# CopterControl_3D.net
KiCad netlist of a schematic drawn in Altium Designer
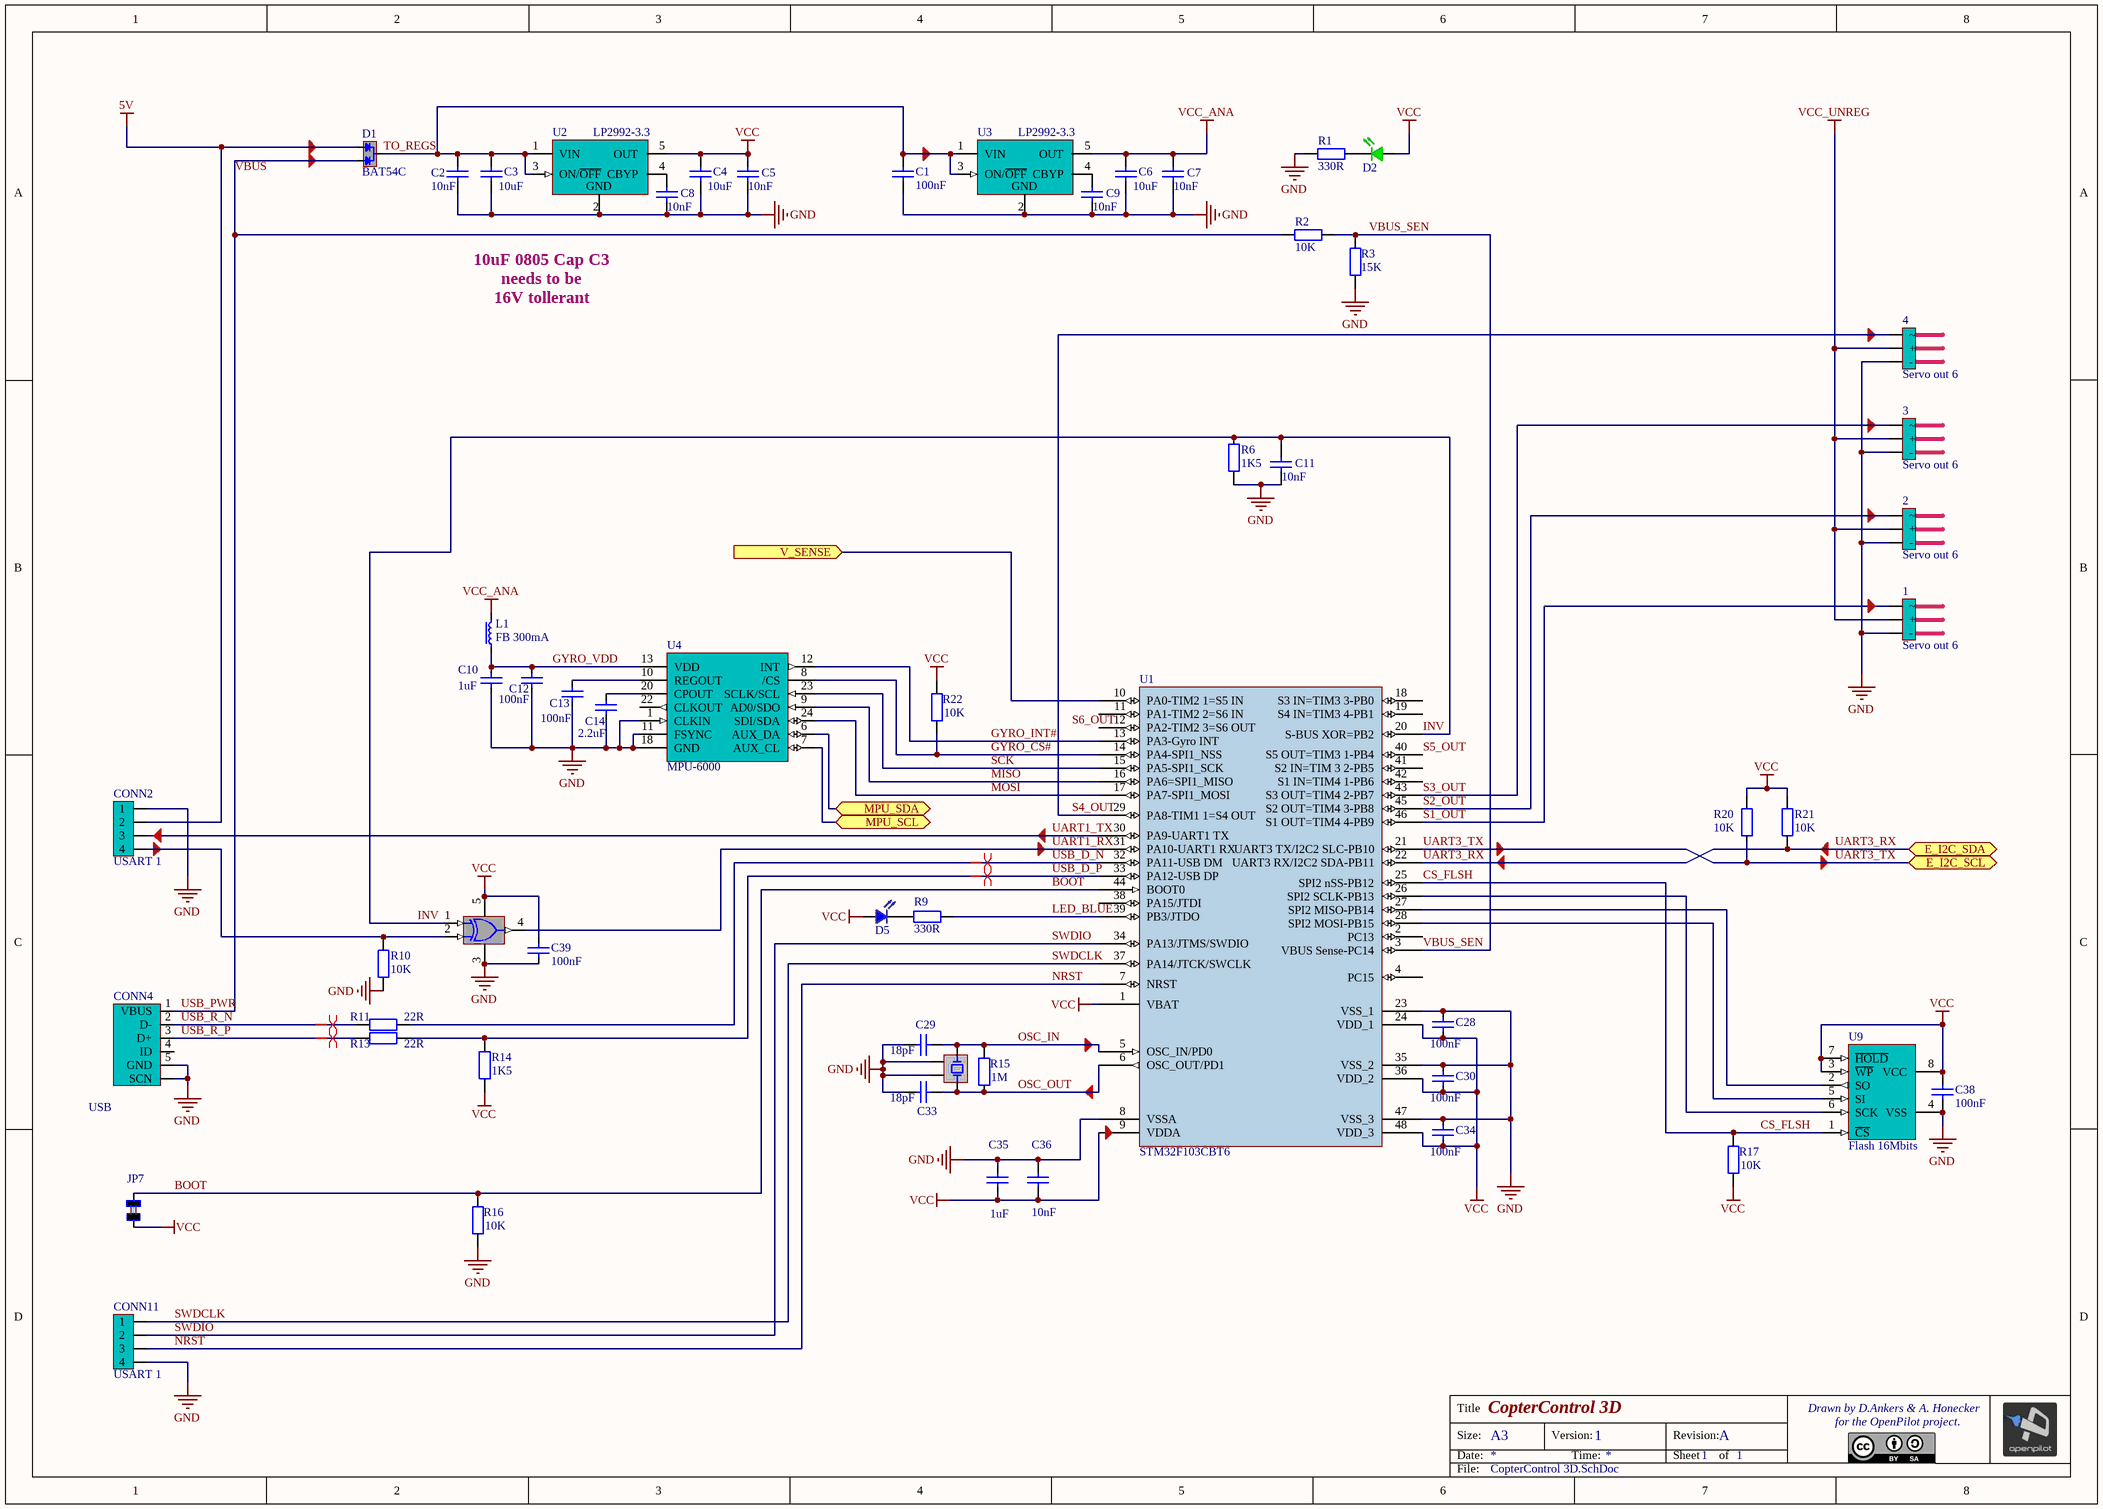
[diagram p0: CopterControl 3D.SchDoc]

(export (version "E")
  (design (tool "Eeschema 10.0.6"))
  (components
    (comp (ref "1")
      (value "Servo out 6")
      (footprint "SIP3 - 0.1")
      (description "Header, 3-Pin, 0.1\"")
      (fields (field (name "MANUFACTURER") "Generic Components"))
      (libsource (lib "CopterControl 3D") (part "Hdr 3 Pin 0.1"))
    )
    (comp (ref "2")
      (value "Servo out 6")
      (footprint "SIP3 - 0.1")
      (description "Header, 3-Pin, 0.1\"")
      (fields (field (name "MANUFACTURER") "Generic Components"))
      (libsource (lib "CopterControl 3D") (part "Hdr 3 Pin 0.1"))
    )
    (comp (ref "3")
      (value "Servo out 6")
      (footprint "SIP3 - 0.1")
      (description "Header, 3-Pin, 0.1\"")
      (fields (field (name "MANUFACTURER") "Generic Components"))
      (libsource (lib "CopterControl 3D") (part "Hdr 3 Pin 0.1"))
    )
    (comp (ref "4")
      (value "Servo out 6")
      (footprint "SIP3 - 0.1")
      (description "Header, 3-Pin, 0.1\"")
      (fields (field (name "MANUFACTURER") "Generic Components"))
      (libsource (lib "CopterControl 3D") (part "Hdr 3 Pin 0.1"))
    )
    (comp (ref "C1")
      (value "100nF")
      (footprint "CAP603N")
      (description "Capacitor SMD")
      (fields (field (name "Comment") "Cap603") (field (name "PUBLISHER") "The OpenPilot Project"))
      (libsource (lib "") (part "Cap603_1"))
    )
    (comp (ref "C2")
      (value "10nF")
      (footprint "CAP603L")
      (description "Capacitor SMD")
      (fields (field (name "Comment") "Cap603") (field (name "PUBLISHER") "The OpenPilot Project"))
      (libsource (lib "") (part "Cap603_1"))
    )
    (comp (ref "C3")
      (value "10uF")
      (footprint "CAP805L")
      (description "Capacitor SMD")
      (fields (field (name "Comment") "Cap805") (field (name "PUBLISHER") "The OpenPilot Project"))
      (libsource (lib "OpenPilot") (part "Cap805"))
    )
    (comp (ref "C4")
      (value "10uF")
      (footprint "CAP805L")
      (description "Capacitor SMD")
      (fields (field (name "Comment") "Cap805") (field (name "PUBLISHER") "The OpenPilot Project"))
      (libsource (lib "OpenPilot") (part "Cap805"))
    )
    (comp (ref "C5")
      (value "10nF")
      (footprint "CAP603N")
      (description "Capacitor SMD")
      (fields (field (name "Comment") "Cap603") (field (name "PUBLISHER") "The OpenPilot Project"))
      (libsource (lib "") (part "Cap603_1"))
    )
    (comp (ref "C6")
      (value "10uF")
      (footprint "CAP805L")
      (description "Capacitor SMD")
      (fields (field (name "Comment") "Cap805") (field (name "PUBLISHER") "The OpenPilot Project"))
      (libsource (lib "OpenPilot") (part "Cap805"))
    )
    (comp (ref "C7")
      (value "10nF")
      (footprint "CAP603N")
      (description "Capacitor SMD")
      (fields (field (name "Comment") "Cap603") (field (name "PUBLISHER") "The OpenPilot Project"))
      (libsource (lib "") (part "Cap603_1"))
    )
    (comp (ref "C8")
      (value "10nF")
      (footprint "CAP603N")
      (description "Capacitor SMD")
      (fields (field (name "Comment") "Cap603") (field (name "PUBLISHER") "The OpenPilot Project"))
      (libsource (lib "") (part "Cap603_1"))
    )
    (comp (ref "C9")
      (value "10nF")
      (footprint "CAP603N")
      (description "Capacitor SMD")
      (fields (field (name "Comment") "Cap603") (field (name "PUBLISHER") "The OpenPilot Project"))
      (libsource (lib "") (part "Cap603_1"))
    )
    (comp (ref "C10")
      (value "1uF")
      (footprint "CAP603L")
      (description "Capacitor SMD")
      (fields (field (name "Comment") "Cap603") (field (name "PUBLISHER") "The OpenPilot Project"))
      (libsource (lib "OpenPilot") (part "Cap603"))
    )
    (comp (ref "C11")
      (value "10nF")
      (footprint "CAP603N")
      (description "Capacitor SMD")
      (fields (field (name "Comment") "Cap603") (field (name "PUBLISHER") "The OpenPilot Project"))
      (libsource (lib "") (part "Cap603_1"))
    )
    (comp (ref "C12")
      (value "100nF")
      (footprint "CAP603L")
      (description "Capacitor SMD")
      (fields (field (name "Comment") "Cap603") (field (name "PUBLISHER") "The OpenPilot Project"))
      (libsource (lib "OpenPilot") (part "Cap603"))
    )
    (comp (ref "C13")
      (value "100nF")
      (footprint "CAP603L")
      (description "Capacitor SMD")
      (fields (field (name "Comment") "Cap603") (field (name "PUBLISHER") "The OpenPilot Project"))
      (libsource (lib "OpenPilot") (part "Cap603"))
    )
    (comp (ref "C14")
      (value "2.2uF")
      (footprint "CAP603L")
      (description "Capacitor SMD")
      (fields (field (name "Comment") "Cap603") (field (name "PUBLISHER") "The OpenPilot Project"))
      (libsource (lib "OpenPilot") (part "Cap603"))
    )
    (comp (ref "C28")
      (value "100nF")
      (footprint "CAP603N")
      (description "Capacitor SMD")
      (fields (field (name "Comment") "Cap603") (field (name "PUBLISHER") "The OpenPilot Project"))
      (libsource (lib "OpenPilot") (part "Cap603"))
    )
    (comp (ref "C29")
      (value "18pF")
      (footprint "CAP603N")
      (description "Capacitor SMD")
      (fields (field (name "Comment") "Cap603") (field (name "PUBLISHER") "The OpenPilot Project"))
      (libsource (lib "") (part "Cap603_1"))
    )
    (comp (ref "C30")
      (value "100nF")
      (footprint "CAP603N")
      (description "Capacitor SMD")
      (fields (field (name "Comment") "Cap603") (field (name "PUBLISHER") "The OpenPilot Project"))
      (libsource (lib "OpenPilot") (part "Cap603"))
    )
    (comp (ref "C33")
      (value "18pF")
      (footprint "CAP603N")
      (description "Capacitor SMD")
      (fields (field (name "Comment") "Cap603") (field (name "PUBLISHER") "The OpenPilot Project"))
      (libsource (lib "") (part "Cap603_1"))
    )
    (comp (ref "C34")
      (value "100nF")
      (footprint "CAP603N")
      (description "Capacitor SMD")
      (fields (field (name "Comment") "Cap603") (field (name "PUBLISHER") "The OpenPilot Project"))
      (libsource (lib "OpenPilot") (part "Cap603"))
    )
    (comp (ref "C35")
      (value "1uF")
      (footprint "CAP603L")
      (description "Capacitor SMD")
      (fields (field (name "Comment") "Cap603") (field (name "PUBLISHER") "The OpenPilot Project"))
      (libsource (lib "OpenPilot") (part "Cap603"))
    )
    (comp (ref "C36")
      (value "10nF")
      (footprint "CAP603N")
      (description "Capacitor SMD")
      (fields (field (name "Comment") "Cap603") (field (name "PUBLISHER") "The OpenPilot Project"))
      (libsource (lib "") (part "Cap603_1"))
    )
    (comp (ref "C38")
      (value "100nF")
      (footprint "CAP603N")
      (description "Capacitor SMD")
      (fields (field (name "Comment") "Cap603") (field (name "PUBLISHER") "The OpenPilot Project"))
      (libsource (lib "") (part "Cap603_1"))
    )
    (comp (ref "C39")
      (value "100nF")
      (footprint "CAP603N")
      (description "Capacitor SMD")
      (fields (field (name "Comment") "Cap603") (field (name "PUBLISHER") "The OpenPilot Project"))
      (libsource (lib "OpenPilot") (part "Cap603"))
    )
    (comp (ref "CONN2")
      (value "USART 1")
      (footprint "JST SH 4 Pin Side Entry")
      (description "JST-SH 4-pin Side Entry Socket")
      (fields (field (name "MANUFACTURER") "Generic Components"))
      (libsource (lib "CopterControl 3D") (part "JST-SH 4-pin Side Entry Socket"))
    )
    (comp (ref "CONN4")
      (value "USB")
      (footprint "USB SMD")
      (description "USB Type-B SMT Socket")
      (libsource (lib "CopterControl 3D") (part "USB_SMT_B"))
    )
    (comp (ref "CONN11")
      (value "USART 1")
      (footprint "JST SH 4 Pin Side Entry")
      (description "JST-SH 4-pin Side Entry Socket")
      (fields (field (name "MANUFACTURER") "Generic Components"))
      (libsource (lib "CopterControl 3D") (part "JST-SH 4-pin Side Entry Socket"))
    )
    (comp (ref "D1")
      (value "BAT54C")
      (footprint "SOT23-3N")
      (description "Dual Diode Command Cathode")
      (libsource (lib "CopterControl 3D") (part "BAT54C"))
    )
    (comp (ref "D2")
      (value "Green")
      (footprint "LED603N")
      (description "Green 603 LED")
      (libsource (lib "OpenPilot") (part "LED 603 Gr"))
    )
    (comp (ref "D5")
      (value "Blue")
      (footprint "LED603N")
      (description "Blue 603 LED")
      (libsource (lib "OpenPilot") (part "LED 603 Bl"))
    )
    (comp (ref "JP7")
      (value "2 PAD Touch JMP")
      (footprint "TOUCH JMP 2PAD")
      (description "2 Pad Touch Jumper")
      (fields (field (name "PUBLISHER") "The OpenPilot Project"))
      (libsource (lib "CopterControl 3D") (part "2 PAD Touch JMP"))
    )
    (comp (ref "L1")
      (value "FB 300mA")
      (footprint "IND603N")
      (description "Ferrite Bead 300mA")
      (fields (field (name "MANUFACTURER") "Generic Components"))
      (libsource (lib "CopterControl 3D") (part "FerriteBead_300mA"))
    )
    (comp (ref "R1")
      (value "330R")
      (footprint "RES603N")
      (description "Resistor SMD")
      (fields (field (name "Comment") "Res603") (field (name "PUBLISHER") "The OpenPilot Project"))
      (libsource (lib "") (part "Res603_4"))
    )
    (comp (ref "R2")
      (value "10K")
      (footprint "RES603N")
      (description "Resistor SMD")
      (fields (field (name "Comment") "Res603") (field (name "PUBLISHER") "The OpenPilot Project"))
      (libsource (lib "") (part "Res603_4"))
    )
    (comp (ref "R3")
      (value "15K")
      (footprint "RES603N")
      (description "Resistor SMD")
      (fields (field (name "Comment") "Res603") (field (name "PUBLISHER") "The OpenPilot Project"))
      (libsource (lib "") (part "Res603_2"))
    )
    (comp (ref "R6")
      (value "1K5")
      (footprint "RES603N")
      (description "Resistor SMD")
      (fields (field (name "Comment") "Res603") (field (name "PUBLISHER") "The OpenPilot Project"))
      (libsource (lib "") (part "Res603_3"))
    )
    (comp (ref "R9")
      (value "330R")
      (footprint "RES603N")
      (description "Resistor SMD")
      (fields (field (name "Comment") "Res603") (field (name "PUBLISHER") "The OpenPilot Project"))
      (libsource (lib "") (part "Res603_4"))
    )
    (comp (ref "R10")
      (value "10K")
      (footprint "RES603N")
      (description "Resistor SMD")
      (fields (field (name "Comment") "Res603") (field (name "PUBLISHER") "The OpenPilot Project"))
      (libsource (lib "") (part "Res603_2"))
    )
    (comp (ref "R11")
      (value "22R")
      (footprint "RES603N")
      (description "Resistor SMD")
      (fields (field (name "Comment") "Res603") (field (name "PUBLISHER") "The OpenPilot Project"))
      (libsource (lib "OpenPilot") (part "Res603"))
    )
    (comp (ref "R13")
      (value "22R")
      (footprint "RES603N")
      (description "Resistor SMD")
      (fields (field (name "Comment") "Res603") (field (name "PUBLISHER") "The OpenPilot Project"))
      (libsource (lib "OpenPilot") (part "Res603"))
    )
    (comp (ref "R14")
      (value "1K5")
      (footprint "RES603N")
      (description "Resistor SMD")
      (fields (field (name "Comment") "Res603") (field (name "PUBLISHER") "The OpenPilot Project"))
      (libsource (lib "") (part "Res603_2"))
    )
    (comp (ref "R15")
      (value "1M")
      (footprint "RES603N")
      (description "Resistor SMD")
      (fields (field (name "Comment") "Res603") (field (name "PUBLISHER") "The OpenPilot Project"))
      (libsource (lib "") (part "Res603_1"))
    )
    (comp (ref "R16")
      (value "10K")
      (footprint "RES603N")
      (description "Resistor SMD")
      (fields (field (name "Comment") "Res603") (field (name "PUBLISHER") "The OpenPilot Project"))
      (libsource (lib "") (part "Res603_2"))
    )
    (comp (ref "R17")
      (value "10K")
      (footprint "RES603N")
      (description "Resistor SMD")
      (fields (field (name "Comment") "Res603") (field (name "PUBLISHER") "The OpenPilot Project"))
      (libsource (lib "") (part "Res603_2"))
    )
    (comp (ref "R20")
      (value "10K")
      (footprint "RES603N")
      (description "Resistor SMD")
      (fields (field (name "Comment") "Res603") (field (name "PUBLISHER") "The OpenPilot Project"))
      (libsource (lib "") (part "Res603_1"))
    )
    (comp (ref "R21")
      (value "10K")
      (footprint "RES603N")
      (description "Resistor SMD")
      (fields (field (name "Comment") "Res603") (field (name "PUBLISHER") "The OpenPilot Project"))
      (libsource (lib "") (part "Res603_2"))
    )
    (comp (ref "R22")
      (value "10K")
      (footprint "RES603N")
      (description "Resistor SMD")
      (fields (field (name "Comment") "Res603") (field (name "PUBLISHER") "The OpenPilot Project"))
      (libsource (lib "") (part "Res603_2"))
    )
    (comp (ref "U1")
      (value "STM32F103CBT6")
      (footprint "STM32 48 Lead")
      (description "STM32 ARM-based 32-bit MCU with 128 Kbytes Flash, 48-pin LQFP, Industrial Temperature")
      (fields (field (name "PUBLISHER") "Altium Limited"))
      (libsource (lib "OpenPilot") (part "STM32F103CBT6"))
    )
    (comp (ref "U2")
      (value "LP2992-3.3")
      (footprint "SOT23-5L")
      (description "3.3V 250mA LDO Regulator")
      (fields
        (field (name "MANUFACTURER") "National Semiconductor")
        (field (name "MANUFACTURER PART NUMBER") "LP2992AIM5-3.3/NOPB")
      )
      (libsource (lib "OpenPilot") (part "LP2985-3.3"))
    )
    (comp (ref "U3")
      (value "LP2992-3.3")
      (footprint "SOT23-5L")
      (description "3.3V 250mA LDO Regulator")
      (fields
        (field (name "MANUFACTURER") "National Semiconductor")
        (field (name "MANUFACTURER PART NUMBER") "LP2992AIM5-3.3/NOPB")
      )
      (libsource (lib "OpenPilot") (part "LP2985-3.3"))
    )
    (comp (ref "U4")
      (value "MPU-6000")
      (footprint "IMU-3000")
      (description "Invensense MPU-3/6000,  3-axis Gyros & Accel on 6000")
      (fields (field (name "MANUFACTURER") "Invensense") (field (name "PUBLISHER") "The OpenPilot Project"))
      (libsource (lib "OpenPilot") (part "MPU-3/6000"))
    )
    (comp (ref "U6")
      (value "XOR")
      (footprint "DCK-5")
      (description "XOR Gate SN74LVC1G86DCKR")
      (libsource (lib "CopterControl 3D") (part "XOR SN74LVC1G86DCKR"))
    )
    (comp (ref "U9")
      (value "Flash 16Mbits")
      (footprint "SOIC8_N")
      (description "16Mbit SPI Flash Memory")
      (fields (field (name "PUBLISHER") "The OpenPilot Project"))
      (libsource (lib "OpenPilot") (part "Flash 16Mb 75MHZ 8SOIC"))
    )
    (comp (ref "X1")
      (value "8MHz")
      (footprint "XTAL ACT530SMX-4 Series")
      (description "Surface Mount Quartz Crystal, Digikey 535-9720-1-ND")
      (libsource (lib "CopterControl 3D") (part "XTAL ACT530SMX-4"))
    )
  )
  (nets
    (net (code "1") (name "/BOOT") (class "Default")
      (node (ref "JP7") (pin "1") (pinfunction "1_1") (pintype "passive"))
      (node (ref "R16") (pin "2") (pinfunction "2_2") (pintype "passive"))
      (node (ref "U1") (pin "44") (pinfunction "BOOT0_44") (pintype "input"))
    )
    (net (code "2") (name "/CS_FLSH") (class "Default")
      (node (ref "R17") (pin "2") (pinfunction "2_2") (pintype "passive"))
      (node (ref "U1") (pin "25") (pinfunction "SPI2_nSS-PB12_25") (pintype "bidirectional"))
      (node (ref "U9") (pin "1") (pinfunction "~{CS}_1") (pintype "input"))
    )
    (net (code "3") (name "/GYRO_CS#") (class "Default")
      (node (ref "R22") (pin "1") (pinfunction "1_1") (pintype "passive"))
      (node (ref "U1") (pin "14") (pinfunction "PA4-SPI1_NSS_14") (pintype "bidirectional"))
      (node (ref "U4") (pin "8") (pinfunction "/CS_8") (pintype "passive"))
    )
    (net (code "4") (name "/GYRO_INT#") (class "Default")
      (node (ref "U1") (pin "13") (pinfunction "PA3-Gyro_INT_13") (pintype "bidirectional"))
      (node (ref "U4") (pin "12") (pinfunction "INT_12") (pintype "output"))
    )
    (net (code "5") (name "/GYRO_VDD") (class "Default")
      (node (ref "C10") (pin "1") (pinfunction "1_1") (pintype "passive"))
      (node (ref "C12") (pin "1") (pinfunction "1_1") (pintype "passive"))
      (node (ref "L1") (pin "1") (pinfunction "1_1") (pintype "passive"))
      (node (ref "U4") (pin "13") (pinfunction "VDD_13") (pintype "power_in"))
    )
    (net (code "6") (name "/INV") (class "Default")
      (node (ref "C11") (pin "1") (pinfunction "1_1") (pintype "passive"))
      (node (ref "R6") (pin "2") (pinfunction "2_2") (pintype "passive"))
      (node (ref "U1") (pin "20") (pinfunction "S-BUS_XOR=PB2_20") (pintype "bidirectional"))
      (node (ref "U6") (pin "1") (pinfunction "A_1") (pintype "input"))
    )
    (net (code "7") (name "/LED_BLUE") (class "Default")
      (node (ref "R9") (pin "2") (pinfunction "2_2") (pintype "passive"))
      (node (ref "U1") (pin "39") (pinfunction "PB3/JTDO_39") (pintype "bidirectional"))
    )
    (net (code "8") (name "/MISO") (class "Default")
      (node (ref "U1") (pin "16") (pinfunction "PA6=SPI1_MISO_16") (pintype "bidirectional"))
      (node (ref "U4") (pin "9") (pinfunction "AD0/SDO_9") (pintype "input"))
    )
    (net (code "9") (name "/MOSI") (class "Default")
      (node (ref "U1") (pin "17") (pinfunction "PA7-SPI1_MOSI_17") (pintype "bidirectional"))
      (node (ref "U4") (pin "24") (pinfunction "SDI/SDA_24") (pintype "bidirectional"))
    )
    (net (code "10") (name "/MPU_SCL") (class "Default")
      (node (ref "U4") (pin "7") (pinfunction "AUX_CL_7") (pintype "bidirectional"))
    )
    (net (code "11") (name "/MPU_SDA") (class "Default")
      (node (ref "U4") (pin "6") (pinfunction "AUX_DA_6") (pintype "bidirectional"))
    )
    (net (code "12") (name "/NRST") (class "Default")
      (node (ref "CONN11") (pin "3") (pinfunction "3_3") (pintype "passive"))
      (node (ref "U1") (pin "7") (pinfunction "NRST_7") (pintype "bidirectional"))
    )
    (net (code "13") (name "/OSC_IN") (class "Default")
      (node (ref "C29") (pin "2") (pinfunction "2_2") (pintype "passive"))
      (node (ref "R15") (pin "2") (pinfunction "2_2") (pintype "passive"))
      (node (ref "U1") (pin "5") (pinfunction "OSC_IN/PD0_5") (pintype "input"))
      (node (ref "X1") (pin "3") (pinfunction "3_3") (pintype "passive"))
    )
    (net (code "14") (name "/OSC_OUT") (class "Default")
      (node (ref "C33") (pin "2") (pinfunction "2_2") (pintype "passive"))
      (node (ref "R15") (pin "1") (pinfunction "1_1") (pintype "passive"))
      (node (ref "U1") (pin "6") (pinfunction "OSC_OUT/PD1_6") (pintype "output"))
      (node (ref "X1") (pin "1") (pinfunction "1_1") (pintype "passive"))
    )
    (net (code "15") (name "/S1_OUT") (class "Default")
      (node (ref "1") (pin "1") (pinfunction "~_1") (pintype "passive"))
      (node (ref "U1") (pin "46") (pinfunction "S1_OUT=TIM4_4-PB9_46") (pintype "bidirectional"))
    )
    (net (code "16") (name "/S2_OUT") (class "Default")
      (node (ref "2") (pin "1") (pinfunction "~_1") (pintype "passive"))
      (node (ref "U1") (pin "45") (pinfunction "S2_OUT=TIM4_3-PB8_45") (pintype "bidirectional"))
    )
    (net (code "17") (name "/S3_OUT") (class "Default")
      (node (ref "3") (pin "1") (pinfunction "~_1") (pintype "passive"))
      (node (ref "U1") (pin "43") (pinfunction "S3_OUT=TIM4_2-PB7_43") (pintype "bidirectional"))
    )
    (net (code "18") (name "/S4_OUT") (class "Default")
      (node (ref "4") (pin "1") (pinfunction "~_1") (pintype "passive"))
      (node (ref "U1") (pin "29") (pinfunction "PA8-TIM1_1=S4_OUT_29") (pintype "bidirectional"))
    )
    (net (code "19") (name "/S5_OUT") (class "Default")
      (node (ref "U1") (pin "40") (pinfunction "S5_OUT=TIM3_1-PB4_40") (pintype "bidirectional"))
    )
    (net (code "21") (name "/SCK") (class "Default")
      (node (ref "U1") (pin "15") (pinfunction "PA5-SPI1_SCK_15") (pintype "bidirectional"))
      (node (ref "U4") (pin "23") (pinfunction "SCLK/SCL_23") (pintype "input"))
    )
    (net (code "22") (name "/SWDCLK") (class "Default")
      (node (ref "CONN11") (pin "1") (pinfunction "1_1") (pintype "passive"))
      (node (ref "U1") (pin "37") (pinfunction "PA14/JTCK/SWCLK_37") (pintype "bidirectional"))
    )
    (net (code "23") (name "/SWDIO") (class "Default")
      (node (ref "CONN11") (pin "2") (pinfunction "2_2") (pintype "passive"))
      (node (ref "U1") (pin "34") (pinfunction "PA13/JTMS/SWDIO_34") (pintype "bidirectional"))
    )
    (net (code "24") (name "/TO_REGS") (class "Default")
      (node (ref "C1") (pin "1") (pinfunction "1_1") (pintype "passive"))
      (node (ref "C2") (pin "1") (pinfunction "1_1") (pintype "passive"))
      (node (ref "C3") (pin "1") (pinfunction "1_1") (pintype "passive"))
      (node (ref "D1") (pin "3") (pinfunction "COM_3") (pintype "passive"))
      (node (ref "U2") (pin "1") (pinfunction "VIN_1") (pintype "power_in"))
      (node (ref "U2") (pin "3") (pinfunction "ON/~{OFF}_3") (pintype "input"))
      (node (ref "U3") (pin "1") (pinfunction "VIN_1") (pintype "power_in"))
      (node (ref "U3") (pin "3") (pinfunction "ON/~{OFF}_3") (pintype "input"))
    )
    (net (code "25") (name "/UART1_RX") (class "Default")
      (node (ref "U1") (pin "31") (pinfunction "PA10-UART1_RX_31") (pintype "bidirectional"))
      (node (ref "U6") (pin "4") (pinfunction "Y_4") (pintype "output"))
    )
    (net (code "26") (name "/UART1_TX") (class "Default")
      (node (ref "CONN2") (pin "3") (pinfunction "3_3") (pintype "passive"))
      (node (ref "U1") (pin "30") (pinfunction "PA9-UART1_TX_30") (pintype "bidirectional"))
    )
    (net (code "27") (name "/UART3_RX") (class "Default")
      (node (ref "R21") (pin "1") (pinfunction "1_1") (pintype "passive"))
      (node (ref "U1") (pin "22") (pinfunction "UART3_RX/I2C2_SDA-PB11_22") (pintype "bidirectional"))
    )
    (net (code "28") (name "/UART3_TX") (class "Default")
      (node (ref "R20") (pin "1") (pinfunction "1_1") (pintype "passive"))
      (node (ref "U1") (pin "21") (pinfunction "UART3_TX/I2C2_SLC-PB10_21") (pintype "bidirectional"))
    )
    (net (code "29") (name "/USB_D_N") (class "Default")
      (node (ref "R11") (pin "1") (pinfunction "1_1") (pintype "passive"))
      (node (ref "U1") (pin "32") (pinfunction "PA11-USB_DM_32") (pintype "bidirectional"))
    )
    (net (code "30") (name "/USB_D_P") (class "Default")
      (node (ref "R13") (pin "1") (pinfunction "1_1") (pintype "passive"))
      (node (ref "R14") (pin "2") (pinfunction "2_2") (pintype "passive"))
      (node (ref "U1") (pin "33") (pinfunction "PA12-USB_DP_33") (pintype "bidirectional"))
    )
    (net (code "31") (name "/USB_PWR") (class "Default")
      (node (ref "CONN4") (pin "1") (pinfunction "VBUS_1") (pintype "passive"))
      (node (ref "D1") (pin "1") (pinfunction "A1_1") (pintype "passive"))
      (node (ref "R2") (pin "1") (pinfunction "1_1") (pintype "passive"))
    )
    (net (code "32") (name "/USB_R_N") (class "Default")
      (node (ref "CONN4") (pin "2") (pinfunction "D-_2") (pintype "passive"))
      (node (ref "R11") (pin "2") (pinfunction "2_2") (pintype "passive"))
    )
    (net (code "33") (name "/USB_R_P") (class "Default")
      (node (ref "CONN4") (pin "3") (pinfunction "D+_3") (pintype "passive"))
      (node (ref "R13") (pin "2") (pinfunction "2_2") (pintype "passive"))
    )
    (net (code "34") (name "/VBUS_SEN") (class "Default")
      (node (ref "R2") (pin "2") (pinfunction "2_2") (pintype "passive"))
      (node (ref "R3") (pin "2") (pinfunction "2_2") (pintype "passive"))
      (node (ref "U1") (pin "3") (pinfunction "VBUS_Sense-PC14_3") (pintype "bidirectional"))
    )
    (net (code "35") (name "/V_SENSE") (class "Default")
      (node (ref "U1") (pin "10") (pinfunction "PA0-TIM2_1=S5_IN_10") (pintype "bidirectional"))
    )
    (net (code "36") (name "5V") (class "Default")
      (node (ref "CONN2") (pin "2") (pinfunction "2_2") (pintype "passive"))
      (node (ref "D1") (pin "2") (pinfunction "A2_2") (pintype "passive"))
    )
    (net (code "37") (name "GND") (class "Default")
      (node (ref "1") (pin "3") (pinfunction "-_3") (pintype "passive"))
      (node (ref "2") (pin "3") (pinfunction "-_3") (pintype "passive"))
      (node (ref "3") (pin "3") (pinfunction "-_3") (pintype "passive"))
      (node (ref "4") (pin "3") (pinfunction "-_3") (pintype "passive"))
      (node (ref "C1") (pin "2") (pinfunction "2_2") (pintype "passive"))
      (node (ref "C10") (pin "2") (pinfunction "2_2") (pintype "passive"))
      (node (ref "C11") (pin "2") (pinfunction "2_2") (pintype "passive"))
      (node (ref "C12") (pin "2") (pinfunction "2_2") (pintype "passive"))
      (node (ref "C13") (pin "2") (pinfunction "2_2") (pintype "passive"))
      (node (ref "C14") (pin "1") (pinfunction "1_1") (pintype "passive"))
      (node (ref "C2") (pin "2") (pinfunction "2_2") (pintype "passive"))
      (node (ref "C28") (pin "1") (pinfunction "1_1") (pintype "passive"))
      (node (ref "C29") (pin "1") (pinfunction "1_1") (pintype "passive"))
      (node (ref "C3") (pin "2") (pinfunction "2_2") (pintype "passive"))
      (node (ref "C30") (pin "1") (pinfunction "1_1") (pintype "passive"))
      (node (ref "C33") (pin "1") (pinfunction "1_1") (pintype "passive"))
      (node (ref "C34") (pin "1") (pinfunction "1_1") (pintype "passive"))
      (node (ref "C35") (pin "2") (pinfunction "2_2") (pintype "passive"))
      (node (ref "C36") (pin "1") (pinfunction "1_1") (pintype "passive"))
      (node (ref "C38") (pin "2") (pinfunction "2_2") (pintype "passive"))
      (node (ref "C39") (pin "2") (pinfunction "2_2") (pintype "passive"))
      (node (ref "C4") (pin "2") (pinfunction "2_2") (pintype "passive"))
      (node (ref "C5") (pin "2") (pinfunction "2_2") (pintype "passive"))
      (node (ref "C6") (pin "2") (pinfunction "2_2") (pintype "passive"))
      (node (ref "C7") (pin "2") (pinfunction "2_2") (pintype "passive"))
      (node (ref "C8") (pin "2") (pinfunction "2_2") (pintype "passive"))
      (node (ref "C9") (pin "2") (pinfunction "2_2") (pintype "passive"))
      (node (ref "CONN11") (pin "4") (pinfunction "4_4") (pintype "passive"))
      (node (ref "CONN2") (pin "1") (pinfunction "1_1") (pintype "passive"))
      (node (ref "CONN4") (pin "0") (pinfunction "SCN_0") (pintype "passive"))
      (node (ref "CONN4") (pin "5") (pinfunction "GND_5") (pintype "passive"))
      (node (ref "R1") (pin "1") (pinfunction "1_1") (pintype "passive"))
      (node (ref "R10") (pin "1") (pinfunction "1_1") (pintype "passive"))
      (node (ref "R16") (pin "1") (pinfunction "1_1") (pintype "passive"))
      (node (ref "R3") (pin "1") (pinfunction "1_1") (pintype "passive"))
      (node (ref "R6") (pin "1") (pinfunction "1_1") (pintype "passive"))
      (node (ref "U1") (pin "23") (pinfunction "VSS_1_23") (pintype "power_in"))
      (node (ref "U1") (pin "35") (pinfunction "VSS_2_35") (pintype "power_in"))
      (node (ref "U1") (pin "47") (pinfunction "VSS_3_47") (pintype "power_in"))
      (node (ref "U1") (pin "8") (pinfunction "VSSA_8") (pintype "power_in"))
      (node (ref "U2") (pin "2") (pinfunction "GND_2") (pintype "power_in"))
      (node (ref "U3") (pin "2") (pinfunction "GND_2") (pintype "power_in"))
      (node (ref "U4") (pin "1") (pinfunction "CLKIN_1") (pintype "input"))
      (node (ref "U4") (pin "11") (pinfunction "FSYNC_11") (pintype "passive"))
      (node (ref "U4") (pin "18") (pinfunction "GND_18") (pintype "power_in"))
      (node (ref "U6") (pin "3") (pinfunction "GND_3") (pintype "power_in"))
      (node (ref "U9") (pin "4") (pinfunction "VSS_4") (pintype "power_in"))
      (node (ref "X1") (pin "2") (pinfunction "2_2") (pintype "passive"))
      (node (ref "X1") (pin "4") (pinfunction "4_4") (pintype "passive"))
    )
    (net (code "38") (name "Net-(D2-K)") (class "Default")
      (node (ref "D2") (pin "1") (pinfunction "K_1") (pintype "passive"))
      (node (ref "R1") (pin "2") (pinfunction "2_2") (pintype "passive"))
    )
    (net (code "39") (name "Net-(D5-K)") (class "Default")
      (node (ref "D5") (pin "1") (pinfunction "K_1") (pintype "passive"))
      (node (ref "R9") (pin "1") (pinfunction "1_1") (pintype "passive"))
    )
    (net (code "40") (name "Net-(U1-SPI2_MISO-PB14)") (class "Default")
      (node (ref "U1") (pin "27") (pinfunction "SPI2_MISO-PB14_27") (pintype "bidirectional"))
      (node (ref "U9") (pin "2") (pinfunction "SO_2") (pintype "output"))
    )
    (net (code "41") (name "Net-(U1-SPI2_MOSI-PB15)") (class "Default")
      (node (ref "U1") (pin "28") (pinfunction "SPI2_MOSI-PB15_28") (pintype "bidirectional"))
      (node (ref "U9") (pin "5") (pinfunction "SI_5") (pintype "input"))
    )
    (net (code "42") (name "Net-(U1-SPI2_SCLK-PB13)") (class "Default")
      (node (ref "U1") (pin "26") (pinfunction "SPI2_SCLK-PB13_26") (pintype "bidirectional"))
      (node (ref "U9") (pin "6") (pinfunction "SCK_6") (pintype "input"))
    )
    (net (code "43") (name "Net-(U2-CBYP)") (class "Default")
      (node (ref "C8") (pin "1") (pinfunction "1_1") (pintype "passive"))
      (node (ref "U2") (pin "4") (pinfunction "CBYP_4") (pintype "passive"))
    )
    (net (code "44") (name "Net-(U3-CBYP)") (class "Default")
      (node (ref "C9") (pin "1") (pinfunction "1_1") (pintype "passive"))
      (node (ref "U3") (pin "4") (pinfunction "CBYP_4") (pintype "passive"))
    )
    (net (code "45") (name "Net-(U4-CPOUT)") (class "Default")
      (node (ref "C14") (pin "2") (pinfunction "2_2") (pintype "passive"))
      (node (ref "U4") (pin "20") (pinfunction "CPOUT_20") (pintype "passive"))
    )
    (net (code "46") (name "Net-(U4-REGOUT)") (class "Default")
      (node (ref "C13") (pin "1") (pinfunction "1_1") (pintype "passive"))
      (node (ref "U4") (pin "10") (pinfunction "REGOUT_10") (pintype "passive"))
    )
    (net (code "47") (name "Net-(U6-B)") (class "Default")
      (node (ref "CONN2") (pin "4") (pinfunction "4_4") (pintype "passive"))
      (node (ref "R10") (pin "2") (pinfunction "2_2") (pintype "passive"))
      (node (ref "U6") (pin "2") (pinfunction "B_2") (pintype "input"))
    )
    (net (code "48") (name "VCC") (class "Default")
      (node (ref "C28") (pin "2") (pinfunction "2_2") (pintype "passive"))
      (node (ref "C30") (pin "2") (pinfunction "2_2") (pintype "passive"))
      (node (ref "C34") (pin "2") (pinfunction "2_2") (pintype "passive"))
      (node (ref "C35") (pin "1") (pinfunction "1_1") (pintype "passive"))
      (node (ref "C36") (pin "2") (pinfunction "2_2") (pintype "passive"))
      (node (ref "C38") (pin "1") (pinfunction "1_1") (pintype "passive"))
      (node (ref "C39") (pin "1") (pinfunction "1_1") (pintype "passive"))
      (node (ref "C4") (pin "1") (pinfunction "1_1") (pintype "passive"))
      (node (ref "C5") (pin "1") (pinfunction "1_1") (pintype "passive"))
      (node (ref "D2") (pin "2") (pinfunction "A_2") (pintype "passive"))
      (node (ref "D5") (pin "2") (pinfunction "A_2") (pintype "passive"))
      (node (ref "JP7") (pin "2") (pinfunction "2_2") (pintype "passive"))
      (node (ref "R14") (pin "1") (pinfunction "1_1") (pintype "passive"))
      (node (ref "R17") (pin "1") (pinfunction "1_1") (pintype "passive"))
      (node (ref "R20") (pin "2") (pinfunction "2_2") (pintype "passive"))
      (node (ref "R21") (pin "2") (pinfunction "2_2") (pintype "passive"))
      (node (ref "R22") (pin "2") (pinfunction "2_2") (pintype "passive"))
      (node (ref "U1") (pin "1") (pinfunction "VBAT_1") (pintype "power_in"))
      (node (ref "U1") (pin "24") (pinfunction "VDD_1_24") (pintype "power_in"))
      (node (ref "U1") (pin "36") (pinfunction "VDD_2_36") (pintype "power_in"))
      (node (ref "U1") (pin "48") (pinfunction "VDD_3_48") (pintype "power_in"))
      (node (ref "U1") (pin "9") (pinfunction "VDDA_9") (pintype "power_in"))
      (node (ref "U2") (pin "5") (pinfunction "OUT_5") (pintype "power_in"))
      (node (ref "U6") (pin "5") (pinfunction "VCC_5") (pintype "power_in"))
      (node (ref "U9") (pin "3") (pinfunction "~{WP}_3") (pintype "input"))
      (node (ref "U9") (pin "7") (pinfunction "~{HOLD}_7") (pintype "input"))
      (node (ref "U9") (pin "8") (pinfunction "VCC_8") (pintype "power_in"))
    )
    (net (code "49") (name "VCC_ANA") (class "Default")
      (node (ref "C6") (pin "1") (pinfunction "1_1") (pintype "passive"))
      (node (ref "C7") (pin "1") (pinfunction "1_1") (pintype "passive"))
      (node (ref "L1") (pin "2") (pinfunction "2_2") (pintype "passive"))
      (node (ref "U3") (pin "5") (pinfunction "OUT_5") (pintype "power_in"))
    )
    (net (code "50") (name "VCC_UNREG") (class "Default")
      (node (ref "1") (pin "2") (pinfunction "+_2") (pintype "passive"))
      (node (ref "2") (pin "2") (pinfunction "+_2") (pintype "passive"))
      (node (ref "3") (pin "2") (pinfunction "+_2") (pintype "passive"))
      (node (ref "4") (pin "2") (pinfunction "+_2") (pintype "passive"))
    )
    (net (code "51") (name "unconnected-(CONN4-ID-Pad4)") (class "Default")
      (node (ref "CONN4") (pin "4") (pinfunction "ID_4") (pintype "passive"))
    )
    (net (code "52") (name "unconnected-(U1-PA1-TIM2_2=S6_IN-Pad11)") (class "Default")
      (node (ref "U1") (pin "11") (pinfunction "PA1-TIM2_2=S6_IN_11") (pintype "bidirectional"))
    )
    (net (code "53") (name "unconnected-(U1-PA2-TIM2_3=S6_OUT-Pad12)") (class "Default")
      (node (ref "U1") (pin "12") (pinfunction "PA2-TIM2_3=S6_OUT_12") (pintype "bidirectional"))
    )
    (net (code "54") (name "unconnected-(U1-PA15{slash}JTDI-Pad38)") (class "Default")
      (node (ref "U1") (pin "38") (pinfunction "PA15/JTDI_38") (pintype "bidirectional"))
    )
    (net (code "55") (name "unconnected-(U1-PC13-Pad2)") (class "Default")
      (node (ref "U1") (pin "2") (pinfunction "PC13_2") (pintype "bidirectional"))
    )
    (net (code "56") (name "unconnected-(U1-PC15-Pad4)") (class "Default")
      (node (ref "U1") (pin "4") (pinfunction "PC15_4") (pintype "bidirectional"))
    )
    (net (code "57") (name "unconnected-(U1-S1_IN=TIM4_1-PB6-Pad42)") (class "Default")
      (node (ref "U1") (pin "42") (pinfunction "S1_IN=TIM4_1-PB6_42") (pintype "bidirectional"))
    )
    (net (code "58") (name "unconnected-(U1-S2_IN=TIM_3_2-PB5-Pad41)") (class "Default")
      (node (ref "U1") (pin "41") (pinfunction "S2_IN=TIM_3_2-PB5_41") (pintype "bidirectional"))
    )
    (net (code "59") (name "unconnected-(U1-S3_IN=TIM3_3-PB0-Pad18)") (class "Default")
      (node (ref "U1") (pin "18") (pinfunction "S3_IN=TIM3_3-PB0_18") (pintype "bidirectional"))
    )
    (net (code "60") (name "unconnected-(U1-S4_IN=TIM3_4-PB1-Pad19)") (class "Default")
      (node (ref "U1") (pin "19") (pinfunction "S4_IN=TIM3_4-PB1_19") (pintype "bidirectional"))
    )
    (net (code "61") (name "unconnected-(U4-CLKOUT-Pad22)") (class "Default")
      (node (ref "U4") (pin "22") (pinfunction "CLKOUT_22") (pintype "output"))
    )
    (net (code "62") (name "unconnected-(U4-NC-Pad2)") (class "Default")
      (node (ref "U4") (pin "2") (pinfunction "NC_2") (pintype "tri_state"))
    )
    (net (code "63") (name "unconnected-(U4-NC-Pad3)") (class "Default")
      (node (ref "U4") (pin "3") (pinfunction "NC_3") (pintype "tri_state"))
    )
    (net (code "64") (name "unconnected-(U4-NC-Pad4)") (class "Default")
      (node (ref "U4") (pin "4") (pinfunction "NC_4") (pintype "tri_state"))
    )
    (net (code "65") (name "unconnected-(U4-NC-Pad5)") (class "Default")
      (node (ref "U4") (pin "5") (pinfunction "NC_5") (pintype "tri_state"))
    )
    (net (code "66") (name "unconnected-(U4-NC-Pad14)") (class "Default")
      (node (ref "U4") (pin "14") (pinfunction "NC_14") (pintype "bidirectional"))
    )
    (net (code "67") (name "unconnected-(U4-NC-Pad15)") (class "Default")
      (node (ref "U4") (pin "15") (pinfunction "NC_15") (pintype "tri_state"))
    )
    (net (code "68") (name "unconnected-(U4-NC-Pad16)") (class "Default")
      (node (ref "U4") (pin "16") (pinfunction "NC_16") (pintype "tri_state"))
    )
    (net (code "69") (name "unconnected-(U4-NC-Pad17)") (class "Default")
      (node (ref "U4") (pin "17") (pinfunction "NC_17") (pintype "tri_state"))
    )
    (net (code "70") (name "unconnected-(U4-RESV-Pad19)") (class "Default")
      (node (ref "U4") (pin "19") (pinfunction "RESV_19") (pintype "passive"))
    )
    (net (code "71") (name "unconnected-(U4-RESV-Pad21)") (class "Default")
      (node (ref "U4") (pin "21") (pinfunction "RESV_21") (pintype "passive"))
    )
  )
)
